# DDS_v1.net
KiCad netlist of a schematic drawn in EAGLE
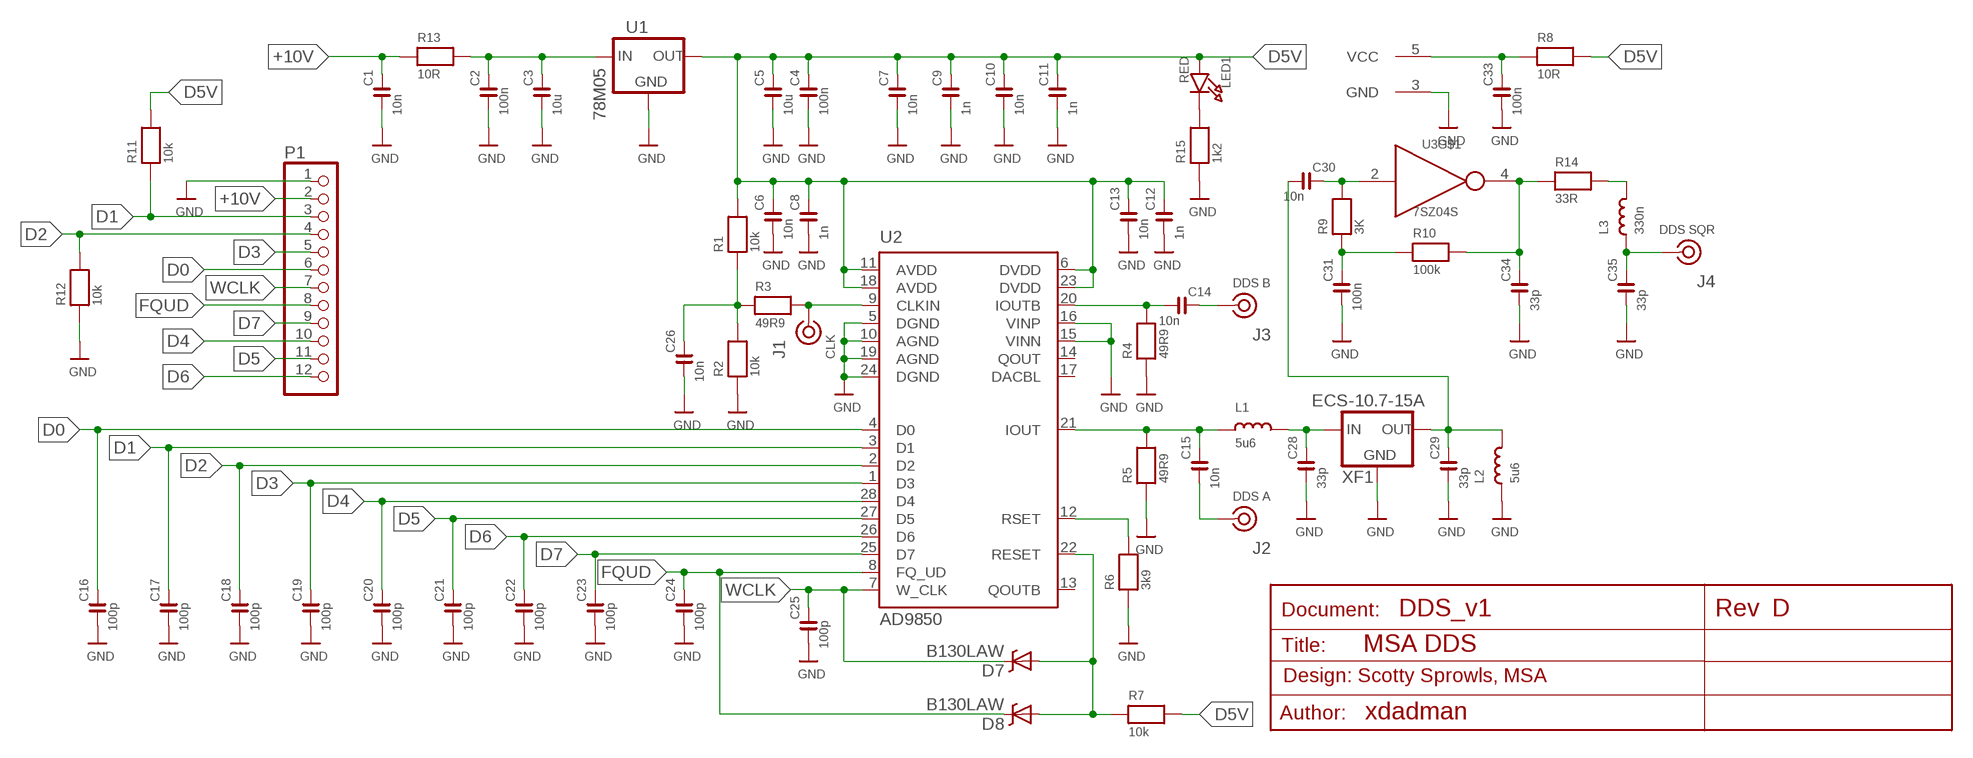
[diagram p0: schematic, sheet 1]

(export (version "E")
  (design (tool "Eeschema 10.0.6"))
  (components
    (comp (ref "C1")
      (value "10n")
      (footprint "eagle-import:C0805")
      (libsource (lib "eagle-import") (part "C080510N"))
    )
    (comp (ref "C2")
      (value "100n")
      (footprint "eagle-import:C0805")
      (libsource (lib "eagle-import") (part "C0805100N"))
    )
    (comp (ref "C3")
      (value "10u")
      (footprint "eagle-import:C1206")
      (libsource (lib "eagle-import") (part "CC120610U"))
    )
    (comp (ref "C4")
      (value "100n")
      (footprint "eagle-import:C0805")
      (libsource (lib "eagle-import") (part "C0805100N"))
    )
    (comp (ref "C5")
      (value "10u")
      (footprint "eagle-import:C1206")
      (libsource (lib "eagle-import") (part "CC120610U"))
    )
    (comp (ref "C6")
      (value "10n")
      (footprint "eagle-import:C0805")
      (libsource (lib "eagle-import") (part "C080510N"))
    )
    (comp (ref "C7")
      (value "10n")
      (footprint "eagle-import:C0805")
      (libsource (lib "eagle-import") (part "C080510N"))
    )
    (comp (ref "C8")
      (value "1n")
      (footprint "eagle-import:C0805")
      (libsource (lib "eagle-import") (part "C08051N"))
    )
    (comp (ref "C9")
      (value "1n")
      (footprint "eagle-import:C0805")
      (libsource (lib "eagle-import") (part "C08051N"))
    )
    (comp (ref "C10")
      (value "10n")
      (footprint "eagle-import:C0805")
      (libsource (lib "eagle-import") (part "C080510N"))
    )
    (comp (ref "C11")
      (value "1n")
      (footprint "eagle-import:C0805")
      (libsource (lib "eagle-import") (part "C08051N"))
    )
    (comp (ref "C12")
      (value "1n")
      (footprint "eagle-import:C0805")
      (libsource (lib "eagle-import") (part "C08051N"))
    )
    (comp (ref "C13")
      (value "10n")
      (footprint "eagle-import:C0805")
      (libsource (lib "eagle-import") (part "C080510N"))
    )
    (comp (ref "C14")
      (value "10n")
      (footprint "eagle-import:C0805")
      (libsource (lib "eagle-import") (part "C080510N"))
    )
    (comp (ref "C15")
      (value "10n")
      (footprint "eagle-import:C0805")
      (libsource (lib "eagle-import") (part "C080510N"))
    )
    (comp (ref "C16")
      (value "100p")
      (footprint "eagle-import:C0805")
      (libsource (lib "eagle-import") (part "C0805100P"))
    )
    (comp (ref "C17")
      (value "100p")
      (footprint "eagle-import:C0805")
      (libsource (lib "eagle-import") (part "C0805100P"))
    )
    (comp (ref "C18")
      (value "100p")
      (footprint "eagle-import:C0805")
      (libsource (lib "eagle-import") (part "C0805100P"))
    )
    (comp (ref "C19")
      (value "100p")
      (footprint "eagle-import:C0805")
      (libsource (lib "eagle-import") (part "C0805100P"))
    )
    (comp (ref "C20")
      (value "100p")
      (footprint "eagle-import:C0805")
      (libsource (lib "eagle-import") (part "C0805100P"))
    )
    (comp (ref "C21")
      (value "100p")
      (footprint "eagle-import:C0805")
      (libsource (lib "eagle-import") (part "C0805100P"))
    )
    (comp (ref "C22")
      (value "100p")
      (footprint "eagle-import:C0805")
      (libsource (lib "eagle-import") (part "C0805100P"))
    )
    (comp (ref "C23")
      (value "100p")
      (footprint "eagle-import:C0805")
      (libsource (lib "eagle-import") (part "C0805100P"))
    )
    (comp (ref "C24")
      (value "100p")
      (footprint "eagle-import:C0805")
      (libsource (lib "eagle-import") (part "C0805100P"))
    )
    (comp (ref "C25")
      (value "100p")
      (footprint "eagle-import:C0805")
      (libsource (lib "eagle-import") (part "C0805100P"))
    )
    (comp (ref "C26")
      (value "10n")
      (footprint "eagle-import:C0805")
      (libsource (lib "eagle-import") (part "C080510N"))
    )
    (comp (ref "C28")
      (value "33p")
      (footprint "eagle-import:C0805")
      (libsource (lib "eagle-import") (part "C080533P"))
    )
    (comp (ref "C29")
      (value "33p")
      (footprint "eagle-import:C0805")
      (libsource (lib "eagle-import") (part "C080533P"))
    )
    (comp (ref "C30")
      (value "10n")
      (footprint "eagle-import:C0805")
      (libsource (lib "eagle-import") (part "C080510N"))
    )
    (comp (ref "C31")
      (value "100n")
      (footprint "eagle-import:C0805")
      (libsource (lib "eagle-import") (part "C0805100N"))
    )
    (comp (ref "C33")
      (value "100n")
      (footprint "eagle-import:C0805")
      (libsource (lib "eagle-import") (part "C0805100N"))
    )
    (comp (ref "C34")
      (value "33p")
      (footprint "eagle-import:C0805")
      (libsource (lib "eagle-import") (part "C080533P"))
    )
    (comp (ref "C35")
      (value "33p")
      (footprint "eagle-import:C0805")
      (libsource (lib "eagle-import") (part "C080533P"))
    )
    (comp (ref "D7")
      (value "B130LAW")
      (footprint "eagle-import:SOD-123")
      (libsource (lib "eagle-import") (part "B130LAW-7-FB130LAW-7-F"))
    )
    (comp (ref "D8")
      (value "B130LAW")
      (footprint "eagle-import:SOD-123")
      (libsource (lib "eagle-import") (part "B130LAW-7-FB130LAW-7-F"))
    )
    (comp (ref "J1")
      (value "CLK")
      (footprint "eagle-import:SLIM_COAX_PAD")
      (libsource (lib "eagle-import") (part "COAX"))
    )
    (comp (ref "J2")
      (value "DDS A")
      (footprint "eagle-import:SLIM_COAX_PAD")
      (libsource (lib "eagle-import") (part "COAX"))
    )
    (comp (ref "J3")
      (value "DDS B")
      (footprint "eagle-import:SLIM_COAX_PAD")
      (libsource (lib "eagle-import") (part "COAX"))
    )
    (comp (ref "J4")
      (value "DDS SQR")
      (footprint "eagle-import:SLIM_COAX_PAD")
      (libsource (lib "eagle-import") (part "COAX"))
    )
    (comp (ref "L1")
      (value "5u6")
      (footprint "eagle-import:L805")
      (libsource (lib "eagle-import") (part "L08055U6"))
    )
    (comp (ref "L2")
      (value "5u6")
      (footprint "eagle-import:L805")
      (libsource (lib "eagle-import") (part "L08055U6"))
    )
    (comp (ref "L3")
      (value "330n")
      (footprint "eagle-import:L805")
      (libsource (lib "eagle-import") (part "L0805330N"))
    )
    (comp (ref "LED1")
      (value "RED")
      (footprint "eagle-import:CHIPLED_0603")
      (libsource (lib "eagle-import") (part "LED_0603_RED0603"))
    )
    (comp (ref "P1")
      (value "PINHD-1X12")
      (footprint "eagle-import:1X12")
      (libsource (lib "eagle-import") (part "PINHD-1X12"))
    )
    (comp (ref "R1")
      (value "10k")
      (footprint "eagle-import:R0805")
      (libsource (lib "eagle-import") (part "R080510K"))
    )
    (comp (ref "R2")
      (value "10k")
      (footprint "eagle-import:R0805")
      (libsource (lib "eagle-import") (part "R080510K"))
    )
    (comp (ref "R3")
      (value "49R9")
      (footprint "eagle-import:R0805")
      (libsource (lib "eagle-import") (part "R080549R9"))
    )
    (comp (ref "R4")
      (value "49R9")
      (footprint "eagle-import:R0805")
      (libsource (lib "eagle-import") (part "R080549R9"))
    )
    (comp (ref "R5")
      (value "49R9")
      (footprint "eagle-import:R0805")
      (libsource (lib "eagle-import") (part "R080549R9"))
    )
    (comp (ref "R6")
      (value "3k9")
      (footprint "eagle-import:R0805")
      (libsource (lib "eagle-import") (part "R08053K9"))
    )
    (comp (ref "R7")
      (value "10k")
      (footprint "eagle-import:R0805")
      (libsource (lib "eagle-import") (part "R080510K"))
    )
    (comp (ref "R8")
      (value "10R")
      (footprint "eagle-import:R0805")
      (libsource (lib "eagle-import") (part "R080510R"))
    )
    (comp (ref "R9")
      (value "3K")
      (footprint "eagle-import:R0805")
      (libsource (lib "eagle-import") (part "R08053K"))
    )
    (comp (ref "R10")
      (value "100k")
      (footprint "eagle-import:R0805")
      (libsource (lib "eagle-import") (part "R0805100K"))
    )
    (comp (ref "R11")
      (value "10k")
      (footprint "eagle-import:R0805")
      (libsource (lib "eagle-import") (part "R080510K"))
    )
    (comp (ref "R12")
      (value "10k")
      (footprint "eagle-import:R0805")
      (libsource (lib "eagle-import") (part "R080510K"))
    )
    (comp (ref "R13")
      (value "10R")
      (footprint "eagle-import:R0805")
      (libsource (lib "eagle-import") (part "R080510R"))
    )
    (comp (ref "R14")
      (value "33R")
      (footprint "eagle-import:R0805")
      (libsource (lib "eagle-import") (part "R080533R"))
    )
    (comp (ref "R15")
      (value "1k2")
      (footprint "eagle-import:R0805")
      (libsource (lib "eagle-import") (part "R08051K2"))
    )
    (comp (ref "U1")
      (value "78M05")
      (footprint "eagle-import:TO252")
      (libsource (lib "eagle-import") (part "78MXXLDPAK"))
    )
    (comp (ref "U2")
      (value "AD9850")
      (footprint "eagle-import:SSOP28")
      (libsource (lib "eagle-import") (part "AD9850"))
    )
    (comp (ref "U3")
      (value "7SZ04S")
      (footprint "eagle-import:SOT23-5L")
      (libsource (lib "eagle-import") (part "7SZ04SOT-23"))
    )
    (comp (ref "XF1")
      (value "ECS-10.7-15A")
      (footprint "eagle-import:XTALFILTER")
      (libsource (lib "eagle-import") (part "XTALFILTER"))
    )
  )
  (nets
    (net (code "1") (name "+10V") (class "Default")
      (node (ref "C1") (pin "2") (pinfunction "2_2") (pintype "passive"))
      (node (ref "P1") (pin "2") (pinfunction "2_2") (pintype "passive"))
      (node (ref "R13") (pin "1") (pinfunction "1_1") (pintype "passive"))
    )
    (net (code "2") (name "D0") (class "Default")
      (node (ref "C16") (pin "2") (pinfunction "2_2") (pintype "passive"))
      (node (ref "P1") (pin "6") (pinfunction "6_6") (pintype "passive"))
      (node (ref "U2") (pin "4") (pinfunction "D0_4") (pintype "bidirectional"))
    )
    (net (code "3") (name "D1") (class "Default")
      (node (ref "C17") (pin "2") (pinfunction "2_2") (pintype "passive"))
      (node (ref "P1") (pin "3") (pinfunction "3_3") (pintype "passive"))
      (node (ref "R11") (pin "1") (pinfunction "1_1") (pintype "passive"))
      (node (ref "U2") (pin "3") (pinfunction "D1_3") (pintype "bidirectional"))
    )
    (net (code "4") (name "D2") (class "Default")
      (node (ref "C18") (pin "2") (pinfunction "2_2") (pintype "passive"))
      (node (ref "P1") (pin "4") (pinfunction "4_4") (pintype "passive"))
      (node (ref "R12") (pin "2") (pinfunction "2_2") (pintype "passive"))
      (node (ref "U2") (pin "2") (pinfunction "D2_2") (pintype "bidirectional"))
    )
    (net (code "5") (name "D3") (class "Default")
      (node (ref "C19") (pin "2") (pinfunction "2_2") (pintype "passive"))
      (node (ref "P1") (pin "5") (pinfunction "5_5") (pintype "passive"))
      (node (ref "U2") (pin "1") (pinfunction "D3_1") (pintype "bidirectional"))
    )
    (net (code "6") (name "D4") (class "Default")
      (node (ref "C20") (pin "2") (pinfunction "2_2") (pintype "passive"))
      (node (ref "P1") (pin "10") (pinfunction "10_10") (pintype "passive"))
      (node (ref "U2") (pin "28") (pinfunction "D4_28") (pintype "bidirectional"))
    )
    (net (code "7") (name "D5") (class "Default")
      (node (ref "C21") (pin "2") (pinfunction "2_2") (pintype "passive"))
      (node (ref "P1") (pin "11") (pinfunction "11_11") (pintype "passive"))
      (node (ref "U2") (pin "27") (pinfunction "D5_27") (pintype "bidirectional"))
    )
    (net (code "8") (name "D5V") (class "Default")
      (node (ref "C10") (pin "2") (pinfunction "2_2") (pintype "passive"))
      (node (ref "C11") (pin "2") (pinfunction "2_2") (pintype "passive"))
      (node (ref "C12") (pin "2") (pinfunction "2_2") (pintype "passive"))
      (node (ref "C13") (pin "2") (pinfunction "2_2") (pintype "passive"))
      (node (ref "C4") (pin "2") (pinfunction "2_2") (pintype "passive"))
      (node (ref "C5") (pin "2") (pinfunction "2_2") (pintype "passive"))
      (node (ref "C6") (pin "2") (pinfunction "2_2") (pintype "passive"))
      (node (ref "C7") (pin "2") (pinfunction "2_2") (pintype "passive"))
      (node (ref "C8") (pin "2") (pinfunction "2_2") (pintype "passive"))
      (node (ref "C9") (pin "2") (pinfunction "2_2") (pintype "passive"))
      (node (ref "LED1") (pin "A") (pinfunction "A_A") (pintype "passive"))
      (node (ref "R1") (pin "2") (pinfunction "2_2") (pintype "passive"))
      (node (ref "R11") (pin "2") (pinfunction "2_2") (pintype "passive"))
      (node (ref "R7") (pin "2") (pinfunction "2_2") (pintype "passive"))
      (node (ref "R8") (pin "2") (pinfunction "2_2") (pintype "passive"))
      (node (ref "U1") (pin "2") (pinfunction "OUT_2") (pintype "passive"))
      (node (ref "U2") (pin "11") (pinfunction "AVDD_11") (pintype "bidirectional"))
      (node (ref "U2") (pin "18") (pinfunction "AVDD_18") (pintype "bidirectional"))
      (node (ref "U2") (pin "23") (pinfunction "DVDD_23") (pintype "bidirectional"))
      (node (ref "U2") (pin "6") (pinfunction "DVDD_6") (pintype "bidirectional"))
    )
    (net (code "9") (name "D6") (class "Default")
      (node (ref "C22") (pin "2") (pinfunction "2_2") (pintype "passive"))
      (node (ref "P1") (pin "12") (pinfunction "12_12") (pintype "passive"))
      (node (ref "U2") (pin "26") (pinfunction "D6_26") (pintype "bidirectional"))
    )
    (net (code "10") (name "D7") (class "Default")
      (node (ref "C23") (pin "2") (pinfunction "2_2") (pintype "passive"))
      (node (ref "P1") (pin "9") (pinfunction "9_9") (pintype "passive"))
      (node (ref "U2") (pin "25") (pinfunction "D7_25") (pintype "bidirectional"))
    )
    (net (code "11") (name "FQUD") (class "Default")
      (node (ref "C24") (pin "2") (pinfunction "2_2") (pintype "passive"))
      (node (ref "D8") (pin "C") (pinfunction "C_C") (pintype "passive"))
      (node (ref "P1") (pin "8") (pinfunction "8_8") (pintype "passive"))
      (node (ref "U2") (pin "8") (pinfunction "FQ_UD_8") (pintype "bidirectional"))
    )
    (net (code "12") (name "GND") (class "Default")
      (node (ref "C1") (pin "1") (pinfunction "1_1") (pintype "passive"))
      (node (ref "C10") (pin "1") (pinfunction "1_1") (pintype "passive"))
      (node (ref "C11") (pin "1") (pinfunction "1_1") (pintype "passive"))
      (node (ref "C12") (pin "1") (pinfunction "1_1") (pintype "passive"))
      (node (ref "C13") (pin "1") (pinfunction "1_1") (pintype "passive"))
      (node (ref "C16") (pin "1") (pinfunction "1_1") (pintype "passive"))
      (node (ref "C17") (pin "1") (pinfunction "1_1") (pintype "passive"))
      (node (ref "C18") (pin "1") (pinfunction "1_1") (pintype "passive"))
      (node (ref "C19") (pin "1") (pinfunction "1_1") (pintype "passive"))
      (node (ref "C2") (pin "1") (pinfunction "1_1") (pintype "passive"))
      (node (ref "C20") (pin "1") (pinfunction "1_1") (pintype "passive"))
      (node (ref "C21") (pin "1") (pinfunction "1_1") (pintype "passive"))
      (node (ref "C22") (pin "1") (pinfunction "1_1") (pintype "passive"))
      (node (ref "C23") (pin "1") (pinfunction "1_1") (pintype "passive"))
      (node (ref "C24") (pin "1") (pinfunction "1_1") (pintype "passive"))
      (node (ref "C25") (pin "1") (pinfunction "1_1") (pintype "passive"))
      (node (ref "C26") (pin "1") (pinfunction "1_1") (pintype "passive"))
      (node (ref "C28") (pin "1") (pinfunction "1_1") (pintype "passive"))
      (node (ref "C29") (pin "1") (pinfunction "1_1") (pintype "passive"))
      (node (ref "C3") (pin "1") (pinfunction "1_1") (pintype "passive"))
      (node (ref "C31") (pin "1") (pinfunction "1_1") (pintype "passive"))
      (node (ref "C33") (pin "1") (pinfunction "1_1") (pintype "passive"))
      (node (ref "C34") (pin "1") (pinfunction "1_1") (pintype "passive"))
      (node (ref "C35") (pin "1") (pinfunction "1_1") (pintype "passive"))
      (node (ref "C4") (pin "1") (pinfunction "1_1") (pintype "passive"))
      (node (ref "C5") (pin "1") (pinfunction "1_1") (pintype "passive"))
      (node (ref "C6") (pin "1") (pinfunction "1_1") (pintype "passive"))
      (node (ref "C7") (pin "1") (pinfunction "1_1") (pintype "passive"))
      (node (ref "C8") (pin "1") (pinfunction "1_1") (pintype "passive"))
      (node (ref "C9") (pin "1") (pinfunction "1_1") (pintype "passive"))
      (node (ref "L2") (pin "1") (pinfunction "1_1") (pintype "passive"))
      (node (ref "P1") (pin "1") (pinfunction "1_1") (pintype "passive"))
      (node (ref "R12") (pin "1") (pinfunction "1_1") (pintype "passive"))
      (node (ref "R15") (pin "1") (pinfunction "1_1") (pintype "passive"))
      (node (ref "R2") (pin "1") (pinfunction "1_1") (pintype "passive"))
      (node (ref "R4") (pin "1") (pinfunction "1_1") (pintype "passive"))
      (node (ref "R5") (pin "1") (pinfunction "1_1") (pintype "passive"))
      (node (ref "R6") (pin "1") (pinfunction "1_1") (pintype "passive"))
      (node (ref "U1") (pin "3") (pinfunction "GND_3") (pintype "input"))
      (node (ref "U2") (pin "10") (pinfunction "AGND_10") (pintype "bidirectional"))
      (node (ref "U2") (pin "15") (pinfunction "VINN_15") (pintype "bidirectional"))
      (node (ref "U2") (pin "16") (pinfunction "VINP_16") (pintype "bidirectional"))
      (node (ref "U2") (pin "19") (pinfunction "AGND_19") (pintype "bidirectional"))
      (node (ref "U2") (pin "24") (pinfunction "DGND_24") (pintype "bidirectional"))
      (node (ref "U2") (pin "5") (pinfunction "DGND_5") (pintype "bidirectional"))
      (node (ref "U3") (pin "3") (pinfunction "GND_3") (pintype "bidirectional"))
      (node (ref "XF1") (pin "3") (pinfunction "GND_3") (pintype "input"))
    )
    (net (code "13") (name "Net-(C26-Pad2)") (class "Default")
      (node (ref "C26") (pin "2") (pinfunction "2_2") (pintype "passive"))
      (node (ref "R1") (pin "1") (pinfunction "1_1") (pintype "passive"))
      (node (ref "R2") (pin "2") (pinfunction "2_2") (pintype "passive"))
      (node (ref "R3") (pin "1") (pinfunction "1_1") (pintype "passive"))
    )
    (net (code "14") (name "Net-(C31-Pad2)") (class "Default")
      (node (ref "C31") (pin "2") (pinfunction "2_2") (pintype "passive"))
      (node (ref "R10") (pin "1") (pinfunction "1_1") (pintype "passive"))
      (node (ref "R9") (pin "1") (pinfunction "1_1") (pintype "passive"))
    )
    (net (code "15") (name "Net-(J1A-1)") (class "Default")
      (node (ref "J1") (pin "SIG") (pinfunction "1_SIG") (pintype "passive"))
      (node (ref "R3") (pin "2") (pinfunction "2_2") (pintype "passive"))
      (node (ref "U2") (pin "9") (pinfunction "CLKIN_9") (pintype "bidirectional"))
    )
    (net (code "16") (name "Net-(J2A-1)") (class "Default")
      (node (ref "C15") (pin "1") (pinfunction "1_1") (pintype "passive"))
      (node (ref "J2") (pin "SIG") (pinfunction "1_SIG") (pintype "passive"))
    )
    (net (code "17") (name "Net-(J3A-1)") (class "Default")
      (node (ref "C14") (pin "2") (pinfunction "2_2") (pintype "passive"))
      (node (ref "J3") (pin "SIG") (pinfunction "1_SIG") (pintype "passive"))
    )
    (net (code "18") (name "Net-(J4A-1)") (class "Default")
      (node (ref "C35") (pin "2") (pinfunction "2_2") (pintype "passive"))
      (node (ref "J4") (pin "SIG") (pinfunction "1_SIG") (pintype "passive"))
      (node (ref "L3") (pin "1") (pinfunction "1_1") (pintype "passive"))
    )
    (net (code "19") (name "Net-(L3-Pad2)") (class "Default")
      (node (ref "L3") (pin "2") (pinfunction "2_2") (pintype "passive"))
      (node (ref "R14") (pin "2") (pinfunction "2_2") (pintype "passive"))
    )
    (net (code "20") (name "Net-(LED1-PadC)") (class "Default")
      (node (ref "LED1") (pin "C") (pinfunction "C_C") (pintype "passive"))
      (node (ref "R15") (pin "2") (pinfunction "2_2") (pintype "passive"))
    )
    (net (code "21") (name "Net-(U1-IN)") (class "Default")
      (node (ref "C2") (pin "2") (pinfunction "2_2") (pintype "passive"))
      (node (ref "C3") (pin "2") (pinfunction "2_2") (pintype "passive"))
      (node (ref "R13") (pin "2") (pinfunction "2_2") (pintype "passive"))
      (node (ref "U1") (pin "1") (pinfunction "IN_1") (pintype "input"))
    )
    (net (code "22") (name "Net-(U2-IOUT)") (class "Default")
      (node (ref "C15") (pin "2") (pinfunction "2_2") (pintype "passive"))
      (node (ref "L1") (pin "1") (pinfunction "1_1") (pintype "passive"))
      (node (ref "R5") (pin "2") (pinfunction "2_2") (pintype "passive"))
      (node (ref "U2") (pin "21") (pinfunction "IOUT_21") (pintype "bidirectional"))
    )
    (net (code "23") (name "Net-(U2-IOUTB)") (class "Default")
      (node (ref "C14") (pin "1") (pinfunction "1_1") (pintype "passive"))
      (node (ref "R4") (pin "2") (pinfunction "2_2") (pintype "passive"))
      (node (ref "U2") (pin "20") (pinfunction "IOUTB_20") (pintype "bidirectional"))
    )
    (net (code "24") (name "Net-(U2-RESET)") (class "Default")
      (node (ref "D7") (pin "A") (pinfunction "A_A") (pintype "passive"))
      (node (ref "D8") (pin "A") (pinfunction "A_A") (pintype "passive"))
      (node (ref "R7") (pin "1") (pinfunction "1_1") (pintype "passive"))
      (node (ref "U2") (pin "22") (pinfunction "RESET_22") (pintype "bidirectional"))
    )
    (net (code "25") (name "Net-(U2-RSET)") (class "Default")
      (node (ref "R6") (pin "2") (pinfunction "2_2") (pintype "passive"))
      (node (ref "U2") (pin "12") (pinfunction "RSET_12") (pintype "bidirectional"))
    )
    (net (code "26") (name "Net-(U3A-IN)") (class "Default")
      (node (ref "C30") (pin "2") (pinfunction "2_2") (pintype "passive"))
      (node (ref "R9") (pin "2") (pinfunction "2_2") (pintype "passive"))
      (node (ref "U3") (pin "2") (pinfunction "IN_2") (pintype "input"))
    )
    (net (code "27") (name "Net-(U3A-OUT)") (class "Default")
      (node (ref "C34") (pin "2") (pinfunction "2_2") (pintype "passive"))
      (node (ref "R10") (pin "2") (pinfunction "2_2") (pintype "passive"))
      (node (ref "R14") (pin "1") (pinfunction "1_1") (pintype "passive"))
      (node (ref "U3") (pin "4") (pinfunction "OUT_4") (pintype "output"))
    )
    (net (code "28") (name "Net-(U3B-VCC)") (class "Default")
      (node (ref "C33") (pin "2") (pinfunction "2_2") (pintype "passive"))
      (node (ref "R8") (pin "1") (pinfunction "1_1") (pintype "passive"))
      (node (ref "U3") (pin "5") (pinfunction "VCC_5") (pintype "bidirectional"))
    )
    (net (code "29") (name "Net-(XF1-IN)") (class "Default")
      (node (ref "C28") (pin "2") (pinfunction "2_2") (pintype "passive"))
      (node (ref "L1") (pin "2") (pinfunction "2_2") (pintype "passive"))
      (node (ref "XF1") (pin "2") (pinfunction "IN_2") (pintype "input"))
    )
    (net (code "30") (name "Net-(XF1-OUT)") (class "Default")
      (node (ref "C29") (pin "2") (pinfunction "2_2") (pintype "passive"))
      (node (ref "C30") (pin "1") (pinfunction "1_1") (pintype "passive"))
      (node (ref "L2") (pin "2") (pinfunction "2_2") (pintype "passive"))
      (node (ref "XF1") (pin "1") (pinfunction "OUT_1") (pintype "passive"))
    )
    (net (code "31") (name "WCLK") (class "Default")
      (node (ref "C25") (pin "2") (pinfunction "2_2") (pintype "passive"))
      (node (ref "D7") (pin "C") (pinfunction "C_C") (pintype "passive"))
      (node (ref "P1") (pin "7") (pinfunction "7_7") (pintype "passive"))
      (node (ref "U2") (pin "7") (pinfunction "W_CLK_7") (pintype "bidirectional"))
    )
    (net (code "32") (name "unconnected-(U2-DACBL-Pad17)") (class "Default")
      (node (ref "U2") (pin "17") (pinfunction "DACBL_17") (pintype "bidirectional"))
    )
    (net (code "33") (name "unconnected-(U2-QOUT-Pad14)") (class "Default")
      (node (ref "U2") (pin "14") (pinfunction "QOUT_14") (pintype "bidirectional"))
    )
    (net (code "34") (name "unconnected-(U2-QOUTB-Pad13)") (class "Default")
      (node (ref "U2") (pin "13") (pinfunction "QOUTB_13") (pintype "bidirectional"))
    )
  )
)
